# 3_waffling60-SI_mcu.net
KiCad netlist of a schematic drawn in Altium Designer
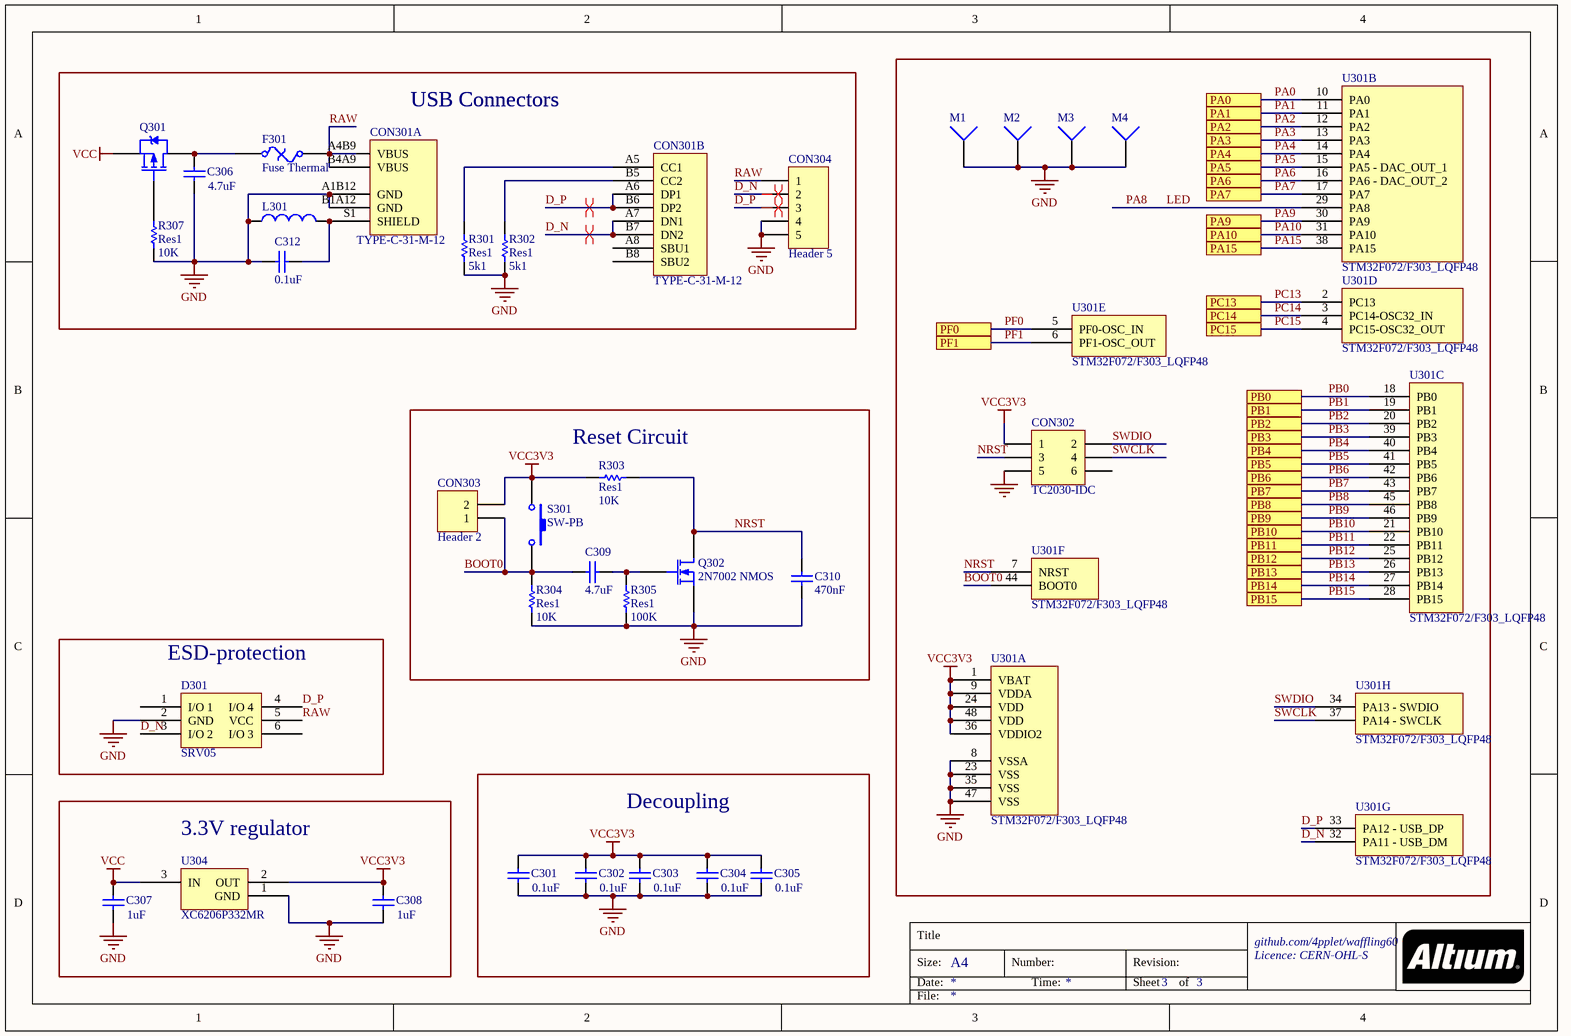
[diagram p0: 3_waffling60-SI_mcu.SchDoc]

(export (version "E")
  (design (tool "Eeschema 10.0.6"))
  (components
    (comp (ref "C301")
      (value "0.1uF")
      (footprint "C0603[1608]")
      (description "Capacitor")
      (fields (field (name "LCSC PART #") "C14663") (field (name "MRF.PART") "CC0603KRX7R9BB104"))
      (libsource (lib "Miscellaneous Devices") (part "Cap"))
    )
    (comp (ref "C302")
      (value "0.1uF")
      (footprint "C0603[1608]")
      (description "Capacitor")
      (fields (field (name "LCSC PART #") "C14663") (field (name "MRF.PART") "CC0603KRX7R9BB104"))
      (libsource (lib "Miscellaneous Devices") (part "Cap"))
    )
    (comp (ref "C303")
      (value "0.1uF")
      (footprint "C0603[1608]")
      (description "Capacitor")
      (fields (field (name "LCSC PART #") "C14663") (field (name "MRF.PART") "CC0603KRX7R9BB104"))
      (libsource (lib "Miscellaneous Devices") (part "Cap"))
    )
    (comp (ref "C304")
      (value "0.1uF")
      (footprint "C0603[1608]")
      (description "Capacitor")
      (fields (field (name "LCSC PART #") "C14663") (field (name "MRF.PART") "CC0603KRX7R9BB104"))
      (libsource (lib "Miscellaneous Devices") (part "Cap"))
    )
    (comp (ref "C305")
      (value "0.1uF")
      (footprint "C0603[1608]")
      (description "Capacitor")
      (fields (field (name "LCSC PART #") "C14663") (field (name "MRF.PART") "CC0603KRX7R9BB104"))
      (libsource (lib "Miscellaneous Devices") (part "Cap"))
    )
    (comp (ref "C306")
      (value "4.7uF")
      (footprint "C0603[1608]")
      (description "Capacitor")
      (fields (field (name "LCSC PART #") "C19666") (field (name "MRF.PART") "CL10A475KO8NNNC"))
      (libsource (lib "Miscellaneous Devices") (part "Cap"))
    )
    (comp (ref "C307")
      (value "1uF")
      (footprint "C0603[1608]")
      (description "Capacitor")
      (fields (field (name "LCSC PART #") "C15849") (field (name "MRF.PART") "CL10A105KB8NNNC"))
      (libsource (lib "Miscellaneous Devices") (part "Cap"))
    )
    (comp (ref "C308")
      (value "1uF")
      (footprint "C0603[1608]")
      (description "Capacitor")
      (fields (field (name "LCSC PART #") "C15849") (field (name "MRF.PART") "CL10A105KB8NNNC"))
      (libsource (lib "Miscellaneous Devices") (part "Cap"))
    )
    (comp (ref "C309")
      (value "4.7uF")
      (footprint "C0603[1608]")
      (description "Capacitor")
      (fields (field (name "LCSC PART #") "C19666") (field (name "MRF.PART") "CL10A475KO8NNNC"))
      (libsource (lib "Miscellaneous Devices") (part "Cap"))
    )
    (comp (ref "C310")
      (value "470nF")
      (footprint "C0603[1608]")
      (description "Capacitor")
      (fields (field (name "LCSC PART #") "C1623") (field (name "MRF.PART") "CL10B474KA8NNNC"))
      (libsource (lib "Miscellaneous Devices") (part "Cap"))
    )
    (comp (ref "C312")
      (value "0.1uF")
      (footprint "C0603[1608]")
      (description "Capacitor")
      (fields (field (name "LCSC PART #") "C14663") (field (name "MRF.PART") "CC0603KRX7R9BB104"))
      (libsource (lib "Miscellaneous Devices") (part "Cap"))
    )
    (comp (ref "CON301")
      (value "TYPE-C-31-M-12")
      (footprint "TYPE-C-31-M-12")
      (fields (field (name "LCSC PART #") "C165948"))
      (libsource (lib "Schlib1") (part "TYPE-C-31-M-12"))
    )
    (comp (ref "CON302")
      (value "TC2030-IDC")
      (footprint "TC2030-IDC-NL")
      (description "Header, 3-Pin, Dual row")
      (libsource (lib "Miscellaneous Connectors") (part "Header 3X2"))
    )
    (comp (ref "CON303")
      (value "Header 2")
      (footprint "HDR1X2")
      (description "Header, 2-Pin")
      (libsource (lib "Miscellaneous Connectors") (part "Header 2"))
    )
    (comp (ref "CON304")
      (value "Header 5")
      (footprint "JST SM04B-SRSS-TB")
      (description "JST for USB daughter board")
      (fields (field (name "LCSC PART #") "C160404") (field (name "MRF.PART") "SM04B-SRSS-TB(LF)(SN)"))
      (libsource (lib "Miscellaneous Connectors") (part "Header 5"))
    )
    (comp (ref "D301")
      (value "SRV05")
      (footprint "SOT-23-6")
      (fields (field (name "LCSC PART #") "C85364") (field (name "MRF.PART") "SRV05-4-P-T7"))
      (libsource (lib "Keebs") (part "SRV05"))
    )
    (comp (ref "F301")
      (value "Fuse Thermal")
      (footprint "C1206[3216]")
      (description "Thermal Fuse")
      (fields (field (name "LCSC PART #") "C135338") (field (name "MRF.PART") "ASMD1206-050"))
      (libsource (lib "Miscellaneous Devices") (part "Fuse Thermal"))
    )
    (comp (ref "L301")
      (value "Inductor")
      (footprint "L0805")
      (fields (field (name "LCSC PART #") "C1015") (field (name "MRF.PART") "GZ2012D101TF"))
      (libsource (lib "Simulation Generic Components") (part "Inductor"))
    )
    (comp (ref "M1")
      (value "Socket")
      (footprint "mounting_hole")
      (libsource (lib "Miscellaneous Connectors") (part "Socket"))
    )
    (comp (ref "M2")
      (value "Socket")
      (footprint "mounting_hole")
      (libsource (lib "Miscellaneous Connectors") (part "Socket"))
    )
    (comp (ref "M3")
      (value "Socket")
      (footprint "mounting_hole")
      (libsource (lib "Miscellaneous Connectors") (part "Socket"))
    )
    (comp (ref "M4")
      (value "Socket")
      (footprint "mounting_hole")
      (libsource (lib "Miscellaneous Connectors") (part "Socket"))
    )
    (comp (ref "Q301")
      (value "PMOS-2")
      (footprint "SOT-23-3")
      (description "P-Channel Power MOSFET")
      (fields (field (name "LCSC PART #") "C10487") (field (name "MRF.PART") "SI2301CDS-T1-GE3"))
      (libsource (lib "Miscellaneous Devices") (part "PMOS-2"))
    )
    (comp (ref "Q302")
      (value "2N7002 NMOS")
      (footprint "SOT-23-3")
      (description "N-Channel MOSFET")
      (fields (field (name "LCSC PART #") "C8545") (field (name "MRF.PART") "2N7002"))
      (libsource (lib "Miscellaneous Devices") (part "MOSFET-N"))
    )
    (comp (ref "R301")
      (value "Res1")
      (footprint "R0603[1608]")
      (description "Resistor")
      (fields
        (field (name "ALTIUM_VALUE") "5k1")
        (field (name "LCSC PART #") "C23186")
        (field (name "MRF.PART") "0603WAF5101T5E")
      )
      (libsource (lib "Miscellaneous Devices") (part "Res1"))
    )
    (comp (ref "R302")
      (value "Res1")
      (footprint "R0603[1608]")
      (description "Resistor")
      (fields
        (field (name "ALTIUM_VALUE") "5k1")
        (field (name "LCSC PART #") "C23186")
        (field (name "MRF.PART") "0603WAF5101T5E")
      )
      (libsource (lib "Miscellaneous Devices") (part "Res1"))
    )
    (comp (ref "R303")
      (value "Res1")
      (footprint "R0603[1608]")
      (description "Resistor")
      (fields
        (field (name "ALTIUM_VALUE") "10K")
        (field (name "LCSC PART #") "C25804")
        (field (name "MRF.PART") "0603WAF1002T5E")
      )
      (libsource (lib "Miscellaneous Devices") (part "Res1"))
    )
    (comp (ref "R304")
      (value "Res1")
      (footprint "R0603[1608]")
      (description "Resistor")
      (fields
        (field (name "ALTIUM_VALUE") "10K")
        (field (name "LCSC PART #") "C25804")
        (field (name "MRF.PART") "0603WAF1002T5E")
      )
      (libsource (lib "Miscellaneous Devices") (part "Res1"))
    )
    (comp (ref "R305")
      (value "Res1")
      (footprint "R0603[1608]")
      (description "Resistor")
      (fields
        (field (name "ALTIUM_VALUE") "100K")
        (field (name "LCSC PART #") "C25803")
        (field (name "MRF.PART") "0603WAF1003T5E")
      )
      (libsource (lib "Miscellaneous Devices") (part "Res1"))
    )
    (comp (ref "R307")
      (value "Res1")
      (footprint "R0603[1608]")
      (description "Resistor")
      (fields
        (field (name "ALTIUM_VALUE") "10K")
        (field (name "LCSC PART #") "C25804")
        (field (name "MRF.PART") "0603WAF1002T5E")
      )
      (libsource (lib "Miscellaneous Devices") (part "Res1"))
    )
    (comp (ref "S301")
      (value "SW-PB")
      (footprint "XKB Switch")
      (description "Switch")
      (fields (field (name "MRF.PART") "TS-1187A-C-D-B") (field (name "LCSC PART #") "C318888"))
      (libsource (lib "Miscellaneous Devices") (part "SW-PB"))
    )
    (comp (ref "U301")
      (value "STM32F072/F303_LQFP48")
      (footprint "STM32 - COMBO 7X7MM")
      (fields (field (name "LCSC PART #") "C915660") (field (name "MRF.PART") "APM32F072CBT6"))
      (libsource (lib "Keebs") (part "STM32F072/F303_LQFP48"))
    )
    (comp (ref "U304")
      (value "XC6206P332MR")
      (footprint "SOT-23-3")
      (fields (field (name "LCSC PART #") "C5446"))
      (libsource (lib "Keebs") (part "SOT23 LDO"))
    )
  )
  (nets
    (net (code "1") (name "/BOOT0") (class "Default")
      (node (ref "C309") (pin "1") (pinfunction "1_1") (pintype "passive"))
      (node (ref "CON303") (pin "1") (pinfunction "1_1") (pintype "passive"))
      (node (ref "R304") (pin "1") (pinfunction "1_1") (pintype "passive"))
      (node (ref "S301") (pin "2") (pinfunction "2_2") (pintype "passive"))
      (node (ref "U301") (pin "44") (pinfunction "BOOT0_44") (pintype "passive"))
    )
    (net (code "2") (name "/D_N") (class "Default")
      (node (ref "CON301") (pin "A7") (pinfunction "DN1_A7") (pintype "passive"))
      (node (ref "CON301") (pin "B7") (pinfunction "DN2_B7") (pintype "passive"))
      (node (ref "CON304") (pin "2") (pinfunction "2_2") (pintype "passive"))
      (node (ref "D301") (pin "3") (pinfunction "I/O_2_3") (pintype "passive"))
      (node (ref "U301") (pin "32") (pinfunction "PA11_-_USB_DM_32") (pintype "passive"))
    )
    (net (code "3") (name "/D_P") (class "Default")
      (node (ref "CON301") (pin "A6") (pinfunction "DP1_A6") (pintype "passive"))
      (node (ref "CON301") (pin "B6") (pinfunction "DP2_B6") (pintype "passive"))
      (node (ref "CON304") (pin "3") (pinfunction "3_3") (pintype "passive"))
      (node (ref "D301") (pin "4") (pinfunction "I/O_4_4") (pintype "passive"))
      (node (ref "U301") (pin "33") (pinfunction "PA12_-_USB_DP_33") (pintype "passive"))
    )
    (net (code "4") (name "/LED") (class "Default")
      (node (ref "U301") (pin "29") (pinfunction "PA8_29") (pintype "passive"))
    )
    (net (code "5") (name "/NRST") (class "Default")
      (node (ref "C310") (pin "1") (pinfunction "1_1") (pintype "passive"))
      (node (ref "CON302") (pin "3") (pinfunction "3_3") (pintype "passive"))
      (node (ref "Q302") (pin "3") (pinfunction "D_3") (pintype "passive"))
      (node (ref "R303") (pin "2") (pinfunction "2_2") (pintype "passive"))
      (node (ref "U301") (pin "7") (pinfunction "NRST_7") (pintype "passive"))
    )
    (net (code "6") (name "/PA0") (class "Default")
      (node (ref "U301") (pin "10") (pinfunction "PA0_10") (pintype "passive"))
    )
    (net (code "7") (name "/PA1") (class "Default")
      (node (ref "U301") (pin "11") (pinfunction "PA1_11") (pintype "passive"))
    )
    (net (code "8") (name "/PA2") (class "Default")
      (node (ref "U301") (pin "12") (pinfunction "PA2_12") (pintype "passive"))
    )
    (net (code "9") (name "/PA3") (class "Default")
      (node (ref "U301") (pin "13") (pinfunction "PA3_13") (pintype "passive"))
    )
    (net (code "10") (name "/PA4") (class "Default")
      (node (ref "U301") (pin "14") (pinfunction "PA4_14") (pintype "passive"))
    )
    (net (code "11") (name "/PA5") (class "Default")
      (node (ref "U301") (pin "15") (pinfunction "PA5_-_DAC_OUT_1_15") (pintype "passive"))
    )
    (net (code "12") (name "/PA6") (class "Default")
      (node (ref "U301") (pin "16") (pinfunction "PA6_-_DAC_OUT_2_16") (pintype "passive"))
    )
    (net (code "13") (name "/PA7") (class "Default")
      (node (ref "U301") (pin "17") (pinfunction "PA7_17") (pintype "passive"))
    )
    (net (code "14") (name "/PA9") (class "Default")
      (node (ref "U301") (pin "30") (pinfunction "PA9_30") (pintype "passive"))
    )
    (net (code "15") (name "/PA10") (class "Default")
      (node (ref "U301") (pin "31") (pinfunction "PA10_31") (pintype "passive"))
    )
    (net (code "16") (name "/PA15") (class "Default")
      (node (ref "U301") (pin "38") (pinfunction "PA15_38") (pintype "passive"))
    )
    (net (code "17") (name "/PB0") (class "Default")
      (node (ref "U301") (pin "18") (pinfunction "PB0_18") (pintype "passive"))
    )
    (net (code "18") (name "/PB1") (class "Default")
      (node (ref "U301") (pin "19") (pinfunction "PB1_19") (pintype "passive"))
    )
    (net (code "19") (name "/PB2") (class "Default")
      (node (ref "U301") (pin "20") (pinfunction "PB2_20") (pintype "passive"))
    )
    (net (code "20") (name "/PB3") (class "Default")
      (node (ref "U301") (pin "39") (pinfunction "PB3_39") (pintype "passive"))
    )
    (net (code "21") (name "/PB4") (class "Default")
      (node (ref "U301") (pin "40") (pinfunction "PB4_40") (pintype "passive"))
    )
    (net (code "22") (name "/PB5") (class "Default")
      (node (ref "U301") (pin "41") (pinfunction "PB5_41") (pintype "passive"))
    )
    (net (code "23") (name "/PB6") (class "Default")
      (node (ref "U301") (pin "42") (pinfunction "PB6_42") (pintype "passive"))
    )
    (net (code "24") (name "/PB7") (class "Default")
      (node (ref "U301") (pin "43") (pinfunction "PB7_43") (pintype "passive"))
    )
    (net (code "25") (name "/PB8") (class "Default")
      (node (ref "U301") (pin "45") (pinfunction "PB8_45") (pintype "passive"))
    )
    (net (code "26") (name "/PB9") (class "Default")
      (node (ref "U301") (pin "46") (pinfunction "PB9_46") (pintype "passive"))
    )
    (net (code "27") (name "/PB10") (class "Default")
      (node (ref "U301") (pin "21") (pinfunction "PB10_21") (pintype "passive"))
    )
    (net (code "28") (name "/PB11") (class "Default")
      (node (ref "U301") (pin "22") (pinfunction "PB11_22") (pintype "passive"))
    )
    (net (code "29") (name "/PB12") (class "Default")
      (node (ref "U301") (pin "25") (pinfunction "PB12_25") (pintype "passive"))
    )
    (net (code "30") (name "/PB13") (class "Default")
      (node (ref "U301") (pin "26") (pinfunction "PB13_26") (pintype "passive"))
    )
    (net (code "31") (name "/PB14") (class "Default")
      (node (ref "U301") (pin "27") (pinfunction "PB14_27") (pintype "passive"))
    )
    (net (code "32") (name "/PB15") (class "Default")
      (node (ref "U301") (pin "28") (pinfunction "PB15_28") (pintype "passive"))
    )
    (net (code "33") (name "/PC13") (class "Default")
      (node (ref "U301") (pin "2") (pinfunction "PC13_2") (pintype "passive"))
    )
    (net (code "34") (name "/PC14") (class "Default")
      (node (ref "U301") (pin "3") (pinfunction "PC14-OSC32_IN_3") (pintype "passive"))
    )
    (net (code "35") (name "/PC15") (class "Default")
      (node (ref "U301") (pin "4") (pinfunction "PC15-OSC32_OUT_4") (pintype "passive"))
    )
    (net (code "36") (name "/PF0") (class "Default")
      (node (ref "U301") (pin "5") (pinfunction "PF0-OSC_IN_5") (pintype "passive"))
    )
    (net (code "37") (name "/PF1") (class "Default")
      (node (ref "U301") (pin "6") (pinfunction "PF1-OSC_OUT_6") (pintype "passive"))
    )
    (net (code "38") (name "/RAW") (class "Default")
      (node (ref "CON301") (pin "A4B9") (pinfunction "VBUS_A4B9") (pintype "passive"))
      (node (ref "CON301") (pin "B4A9") (pinfunction "VBUS_B4A9") (pintype "passive"))
      (node (ref "CON304") (pin "1") (pinfunction "1_1") (pintype "passive"))
      (node (ref "D301") (pin "5") (pinfunction "VCC_5") (pintype "passive"))
      (node (ref "F301") (pin "2") (pinfunction "2_2") (pintype "passive"))
    )
    (net (code "39") (name "/SWCLK") (class "Default")
      (node (ref "CON302") (pin "4") (pinfunction "4_4") (pintype "passive"))
      (node (ref "U301") (pin "37") (pinfunction "PA14_-_SWCLK_37") (pintype "passive"))
    )
    (net (code "40") (name "/SWDIO") (class "Default")
      (node (ref "CON302") (pin "2") (pinfunction "2_2") (pintype "passive"))
      (node (ref "U301") (pin "34") (pinfunction "PA13_-_SWDIO_34") (pintype "passive"))
    )
    (net (code "41") (name "GND") (class "Default")
      (node (ref "C301") (pin "1") (pinfunction "1_1") (pintype "passive"))
      (node (ref "C302") (pin "1") (pinfunction "1_1") (pintype "passive"))
      (node (ref "C303") (pin "1") (pinfunction "1_1") (pintype "passive"))
      (node (ref "C304") (pin "1") (pinfunction "1_1") (pintype "passive"))
      (node (ref "C305") (pin "1") (pinfunction "1_1") (pintype "passive"))
      (node (ref "C306") (pin "1") (pinfunction "1_1") (pintype "passive"))
      (node (ref "C307") (pin "1") (pinfunction "1_1") (pintype "passive"))
      (node (ref "C308") (pin "1") (pinfunction "1_1") (pintype "passive"))
      (node (ref "C310") (pin "2") (pinfunction "2_2") (pintype "passive"))
      (node (ref "C312") (pin "1") (pinfunction "1_1") (pintype "passive"))
      (node (ref "CON301") (pin "A1B12") (pinfunction "GND_A1B12") (pintype "passive"))
      (node (ref "CON301") (pin "B1A12") (pinfunction "GND_B1A12") (pintype "passive"))
      (node (ref "CON302") (pin "5") (pinfunction "5_5") (pintype "passive"))
      (node (ref "CON304") (pin "4") (pinfunction "4_4") (pintype "passive"))
      (node (ref "CON304") (pin "5") (pinfunction "5_5") (pintype "passive"))
      (node (ref "D301") (pin "2") (pinfunction "GND_2") (pintype "passive"))
      (node (ref "L301") (pin "1") (pinfunction "1_1") (pintype "passive"))
      (node (ref "M1") (pin "1") (pinfunction "1_1") (pintype "passive"))
      (node (ref "M2") (pin "1") (pinfunction "1_1") (pintype "passive"))
      (node (ref "M3") (pin "1") (pinfunction "1_1") (pintype "passive"))
      (node (ref "M4") (pin "1") (pinfunction "1_1") (pintype "passive"))
      (node (ref "Q302") (pin "2") (pinfunction "S_2") (pintype "passive"))
      (node (ref "R301") (pin "2") (pinfunction "2_2") (pintype "passive"))
      (node (ref "R302") (pin "2") (pinfunction "2_2") (pintype "passive"))
      (node (ref "R304") (pin "2") (pinfunction "2_2") (pintype "passive"))
      (node (ref "R305") (pin "2") (pinfunction "2_2") (pintype "passive"))
      (node (ref "R307") (pin "2") (pinfunction "2_2") (pintype "passive"))
      (node (ref "U301") (pin "23") (pinfunction "VSS_23") (pintype "passive"))
      (node (ref "U301") (pin "35") (pinfunction "VSS_35") (pintype "passive"))
      (node (ref "U301") (pin "47") (pinfunction "VSS_47") (pintype "passive"))
      (node (ref "U301") (pin "8") (pinfunction "VSSA_8") (pintype "passive"))
      (node (ref "U304") (pin "1") (pinfunction "GND_1") (pintype "passive"))
    )
    (net (code "42") (name "Net-(CON301A-SHIELD)") (class "Default")
      (node (ref "C312") (pin "2") (pinfunction "2_2") (pintype "passive"))
      (node (ref "CON301") (pin "S1") (pinfunction "SHIELD_S1") (pintype "passive"))
      (node (ref "L301") (pin "2") (pinfunction "2_2") (pintype "passive"))
    )
    (net (code "43") (name "Net-(CON301B-CC1)") (class "Default")
      (node (ref "CON301") (pin "A5") (pinfunction "CC1_A5") (pintype "passive"))
      (node (ref "R301") (pin "1") (pinfunction "1_1") (pintype "passive"))
    )
    (net (code "44") (name "Net-(CON301B-CC2)") (class "Default")
      (node (ref "CON301") (pin "B5") (pinfunction "CC2_B5") (pintype "passive"))
      (node (ref "R302") (pin "1") (pinfunction "1_1") (pintype "passive"))
    )
    (net (code "45") (name "Net-(Q301-D)") (class "Default")
      (node (ref "C306") (pin "2") (pinfunction "2_2") (pintype "passive"))
      (node (ref "F301") (pin "1") (pinfunction "1_1") (pintype "passive"))
      (node (ref "Q301") (pin "3") (pinfunction "D_3") (pintype "passive"))
    )
    (net (code "46") (name "Net-(Q301-G)") (class "Default")
      (node (ref "Q301") (pin "1") (pinfunction "G_1") (pintype "passive"))
      (node (ref "R307") (pin "1") (pinfunction "1_1") (pintype "passive"))
    )
    (net (code "47") (name "Net-(Q302-G)") (class "Default")
      (node (ref "C309") (pin "2") (pinfunction "2_2") (pintype "passive"))
      (node (ref "Q302") (pin "1") (pinfunction "G_1") (pintype "passive"))
      (node (ref "R305") (pin "1") (pinfunction "1_1") (pintype "passive"))
    )
    (net (code "48") (name "VCC") (class "Default")
      (node (ref "C307") (pin "2") (pinfunction "2_2") (pintype "passive"))
      (node (ref "Q301") (pin "2") (pinfunction "S_2") (pintype "passive"))
      (node (ref "U304") (pin "3") (pinfunction "IN_3") (pintype "passive"))
    )
    (net (code "49") (name "VCC3V3") (class "Default")
      (node (ref "C301") (pin "2") (pinfunction "2_2") (pintype "passive"))
      (node (ref "C302") (pin "2") (pinfunction "2_2") (pintype "passive"))
      (node (ref "C303") (pin "2") (pinfunction "2_2") (pintype "passive"))
      (node (ref "C304") (pin "2") (pinfunction "2_2") (pintype "passive"))
      (node (ref "C305") (pin "2") (pinfunction "2_2") (pintype "passive"))
      (node (ref "C308") (pin "2") (pinfunction "2_2") (pintype "passive"))
      (node (ref "CON302") (pin "1") (pinfunction "1_1") (pintype "passive"))
      (node (ref "CON303") (pin "2") (pinfunction "2_2") (pintype "passive"))
      (node (ref "R303") (pin "1") (pinfunction "1_1") (pintype "passive"))
      (node (ref "S301") (pin "1") (pinfunction "1_1") (pintype "passive"))
      (node (ref "U301") (pin "1") (pinfunction "VBAT_1") (pintype "passive"))
      (node (ref "U301") (pin "24") (pinfunction "VDD_24") (pintype "passive"))
      (node (ref "U301") (pin "36") (pinfunction "VDDIO2_36") (pintype "passive"))
      (node (ref "U301") (pin "48") (pinfunction "VDD_48") (pintype "passive"))
      (node (ref "U301") (pin "9") (pinfunction "VDDA_9") (pintype "passive"))
      (node (ref "U304") (pin "2") (pinfunction "OUT_2") (pintype "passive"))
    )
    (net (code "50") (name "unconnected-(CON301B-SBU1-PadA8)") (class "Default")
      (node (ref "CON301") (pin "A8") (pinfunction "SBU1_A8") (pintype "passive"))
    )
    (net (code "51") (name "unconnected-(CON301B-SBU2-PadB8)") (class "Default")
      (node (ref "CON301") (pin "B8") (pinfunction "SBU2_B8") (pintype "passive"))
    )
    (net (code "52") (name "unconnected-(CON302-Pad6)") (class "Default")
      (node (ref "CON302") (pin "6") (pinfunction "6_6") (pintype "passive"))
    )
    (net (code "53") (name "unconnected-(D301-I{slash}O_1-Pad1)") (class "Default")
      (node (ref "D301") (pin "1") (pinfunction "I/O_1_1") (pintype "passive"))
    )
    (net (code "54") (name "unconnected-(D301-I{slash}O_3-Pad6)") (class "Default")
      (node (ref "D301") (pin "6") (pinfunction "I/O_3_6") (pintype "passive"))
    )
  )
)
